# Sheet1.net
KiCad netlist of a schematic drawn in Altium Designer
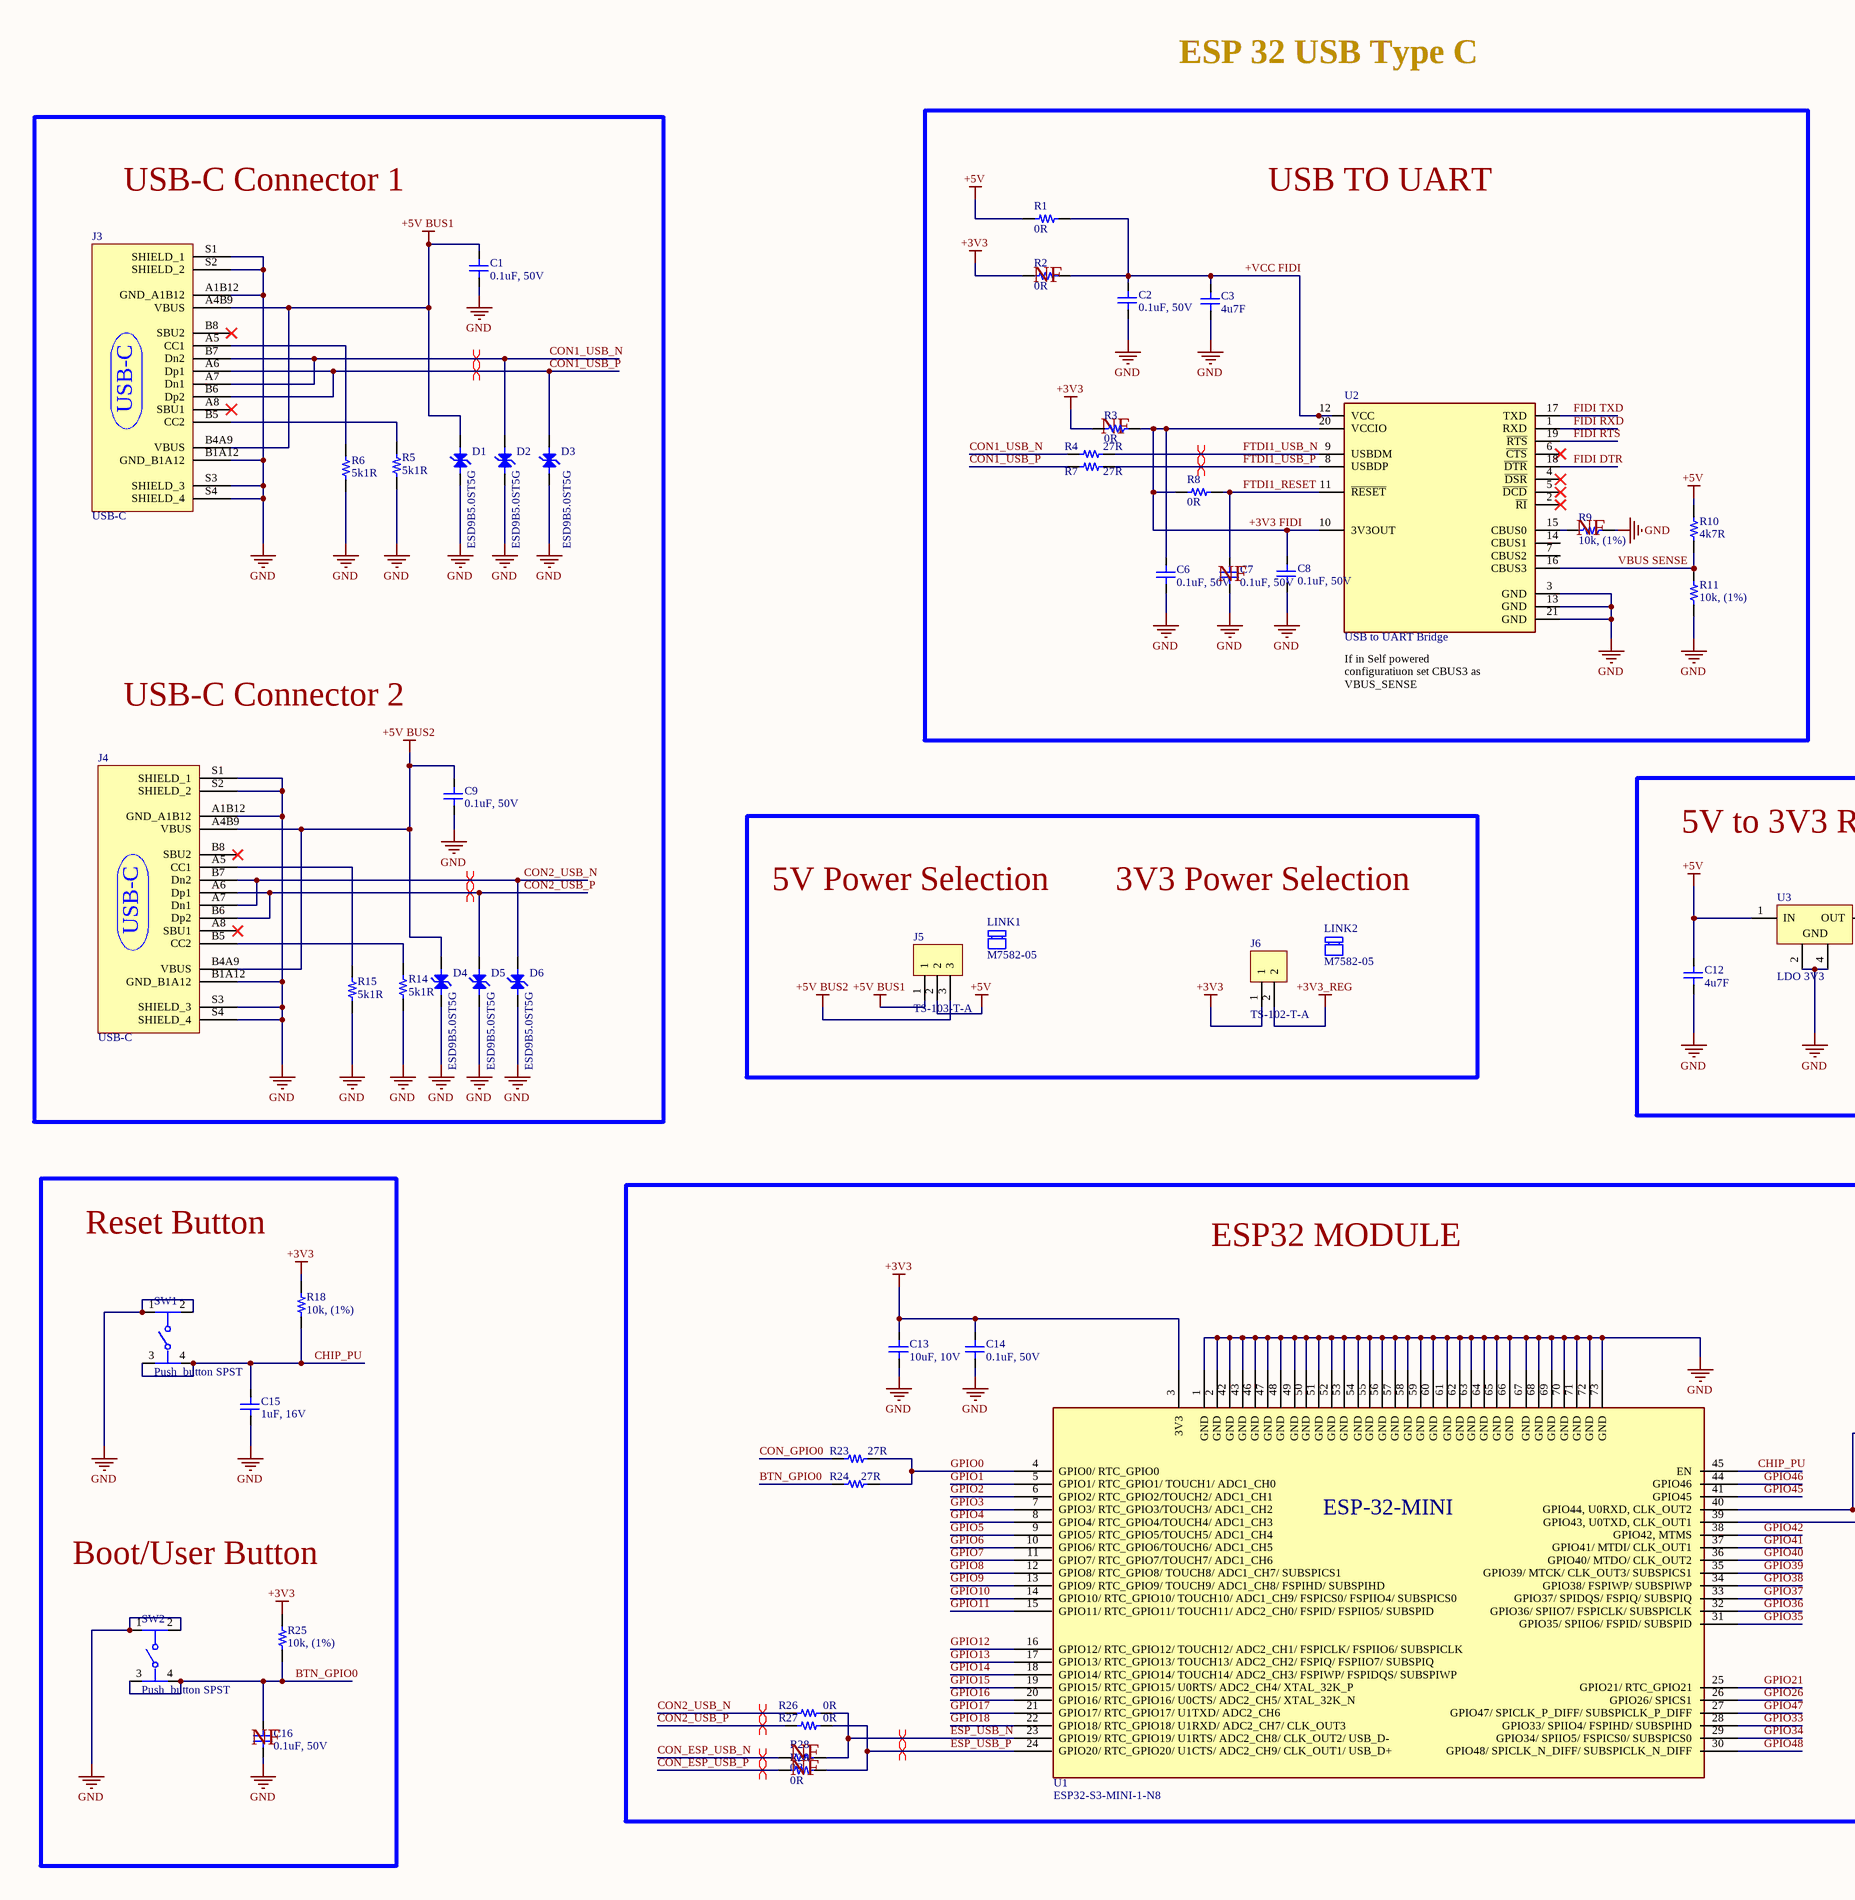
[diagram p0: Sheet1.SchDoc, left]
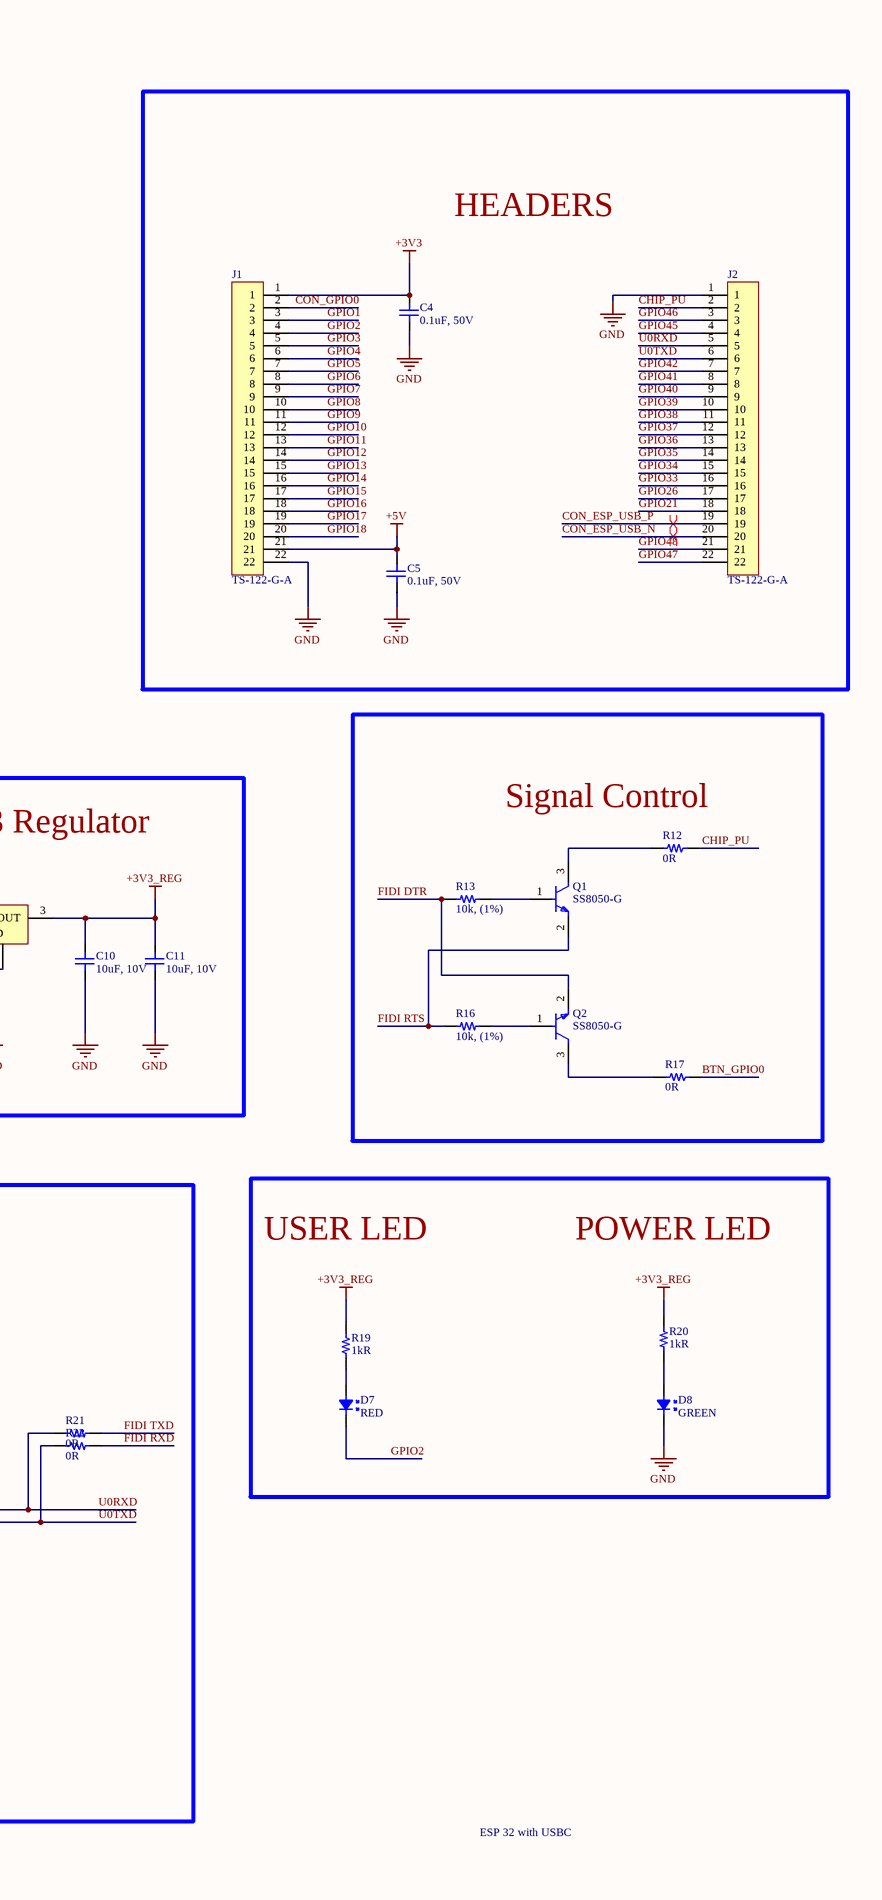
[diagram p1: Sheet1.SchDoc, right]

(export (version "E")
  (design (tool "Eeschema 10.0.6"))
  (components
    (comp (ref "C1")
      (value "0.1uF, 50V")
      (footprint "FP-CL599-IPC_B")
      (description "50V 100nF X7R ±10% 0402 Multilayer Ceramic Capacitors MLCC - SMD/SMT ROHS")
      (fields
        (field (name "MANUFACTURER") "Samsung")
        (field (name "MANUFACTURER PART NUMBER") "CL05B104KB54PNC")
      )
      (libsource (lib "Schlib1") (part "CL05B104KB54PNC"))
    )
    (comp (ref "C2")
      (value "0.1uF, 50V")
      (footprint "FP-CL599-IPC_B")
      (description "50V 100nF X7R ±10% 0402 Multilayer Ceramic Capacitors MLCC - SMD/SMT ROHS")
      (fields
        (field (name "MANUFACTURER") "Samsung")
        (field (name "MANUFACTURER PART NUMBER") "CL05B104KB54PNC")
      )
      (libsource (lib "Schlib1") (part "CL05B104KB54PNC"))
    )
    (comp (ref "C3")
      (value "4u7F")
      (footprint "FP-CL599-IPC_B")
      (description "Multilayer Ceramic Capacitor, 4.7 uF, 10 V, ï¿½ 20%, X5R, 0402 [1005 Metric]")
      (fields
        (field (name "MANUFACTURER") "Samsung")
        (field (name "MANUFACTURER PART NUMBER") "CL05A475MP5NRNC")
      )
      (libsource (lib "Schlib1") (part "CL05A475MP5NRNC"))
    )
    (comp (ref "C4")
      (value "0.1uF, 50V")
      (footprint "FP-CL599-IPC_B")
      (description "50V 100nF X7R ±10% 0402 Multilayer Ceramic Capacitors MLCC - SMD/SMT ROHS")
      (fields
        (field (name "MANUFACTURER") "Samsung")
        (field (name "MANUFACTURER PART NUMBER") "CL05B104KB54PNC")
      )
      (libsource (lib "Schlib1") (part "CL05B104KB54PNC"))
    )
    (comp (ref "C5")
      (value "0.1uF, 50V")
      (footprint "FP-CL599-IPC_B")
      (description "50V 100nF X7R ±10% 0402 Multilayer Ceramic Capacitors MLCC - SMD/SMT ROHS")
      (fields
        (field (name "MANUFACTURER") "Samsung")
        (field (name "MANUFACTURER PART NUMBER") "CL05B104KB54PNC")
      )
      (libsource (lib "Schlib1") (part "CL05B104KB54PNC"))
    )
    (comp (ref "C6")
      (value "0.1uF, 50V")
      (footprint "FP-CL599-IPC_B")
      (description "50V 100nF X7R ±10% 0402 Multilayer Ceramic Capacitors MLCC - SMD/SMT ROHS")
      (fields
        (field (name "MANUFACTURER") "Samsung")
        (field (name "MANUFACTURER PART NUMBER") "CL05B104KB54PNC")
      )
      (libsource (lib "Schlib1") (part "CL05B104KB54PNC"))
    )
    (comp (ref "C7")
      (value "0.1uF, 50V")
      (footprint "FP-CL599-IPC_B")
      (description "50V 100nF X7R ±10% 0402 Multilayer Ceramic Capacitors MLCC - SMD/SMT ROHS")
      (fields
        (field (name "MANUFACTURER") "Samsung")
        (field (name "MANUFACTURER PART NUMBER") "CL05B104KB54PNC")
      )
      (libsource (lib "Schlib1") (part "CL05B104KB54PNC"))
    )
    (comp (ref "C8")
      (value "0.1uF, 50V")
      (footprint "FP-CL599-IPC_B")
      (description "50V 100nF X7R ±10% 0402 Multilayer Ceramic Capacitors MLCC - SMD/SMT ROHS")
      (fields
        (field (name "MANUFACTURER") "Samsung")
        (field (name "MANUFACTURER PART NUMBER") "CL05B104KB54PNC")
      )
      (libsource (lib "Schlib1") (part "CL05B104KB54PNC"))
    )
    (comp (ref "C9")
      (value "0.1uF, 50V")
      (footprint "FP-CL599-IPC_B")
      (description "50V 100nF X7R ±10% 0402 Multilayer Ceramic Capacitors MLCC - SMD/SMT ROHS")
      (fields
        (field (name "MANUFACTURER") "Samsung")
        (field (name "MANUFACTURER PART NUMBER") "CL05B104KB54PNC")
      )
      (libsource (lib "Schlib1") (part "CL05B104KB54PNC"))
    )
    (comp (ref "C10")
      (value "10uF, 10V")
      (footprint "FP-CL599-IPC_B")
      (description "Multilayer Ceramic Capacitor, 10 uF, 10 V, ± 20%, X5R, 0402 [1005 Metric]")
      (fields
        (field (name "MANUFACTURER") "Samsung")
        (field (name "MANUFACTURER PART NUMBER") "CL05A106MP8NUB8")
      )
      (libsource (lib "Schlib1") (part "CL05A106MP8NUB8"))
    )
    (comp (ref "C11")
      (value "10uF, 10V")
      (footprint "FP-CL599-IPC_B")
      (description "Multilayer Ceramic Capacitor, 10 uF, 10 V, ± 20%, X5R, 0402 [1005 Metric]")
      (fields
        (field (name "MANUFACTURER") "Samsung")
        (field (name "MANUFACTURER PART NUMBER") "CL05A106MP8NUB8")
      )
      (libsource (lib "Schlib1") (part "CL05A106MP8NUB8"))
    )
    (comp (ref "C12")
      (value "4u7F")
      (footprint "FP-CL599-IPC_B")
      (description "Multilayer Ceramic Capacitor, 4.7 uF, 10 V, ï¿½ 20%, X5R, 0402 [1005 Metric]")
      (fields
        (field (name "MANUFACTURER") "Samsung")
        (field (name "MANUFACTURER PART NUMBER") "CL05A475MP5NRNC")
      )
      (libsource (lib "Schlib1") (part "CL05A475MP5NRNC"))
    )
    (comp (ref "C13")
      (value "10uF, 10V")
      (footprint "FP-CL599-IPC_B")
      (description "Multilayer Ceramic Capacitor, 10 uF, 10 V, ± 20%, X5R, 0402 [1005 Metric]")
      (fields
        (field (name "MANUFACTURER") "Samsung")
        (field (name "MANUFACTURER PART NUMBER") "CL05A106MP8NUB8")
      )
      (libsource (lib "Schlib1") (part "CL05A106MP8NUB8"))
    )
    (comp (ref "C14")
      (value "0.1uF, 50V")
      (footprint "FP-CL599-IPC_B")
      (description "50V 100nF X7R ±10% 0402 Multilayer Ceramic Capacitors MLCC - SMD/SMT ROHS")
      (fields
        (field (name "MANUFACTURER") "Samsung")
        (field (name "MANUFACTURER PART NUMBER") "CL05B104KB54PNC")
      )
      (libsource (lib "Schlib1") (part "CL05B104KB54PNC"))
    )
    (comp (ref "C15")
      (value "1uF, 16V")
      (footprint "FP-CL599-IPC_B")
      (description "16V 1uF X5R ±10% 0402 Multilayer Ceramic Capacitors MLCC - SMD/SMT ROHS")
      (fields
        (field (name "MANUFACTURER") "Samsung")
        (field (name "MANUFACTURER PART NUMBER") "CL05A105KO5NNNC")
      )
      (libsource (lib "Schlib1") (part "CL05A105KO5NNNC"))
    )
    (comp (ref "C16")
      (value "0.1uF, 50V")
      (footprint "FP-CL599-IPC_B")
      (description "50V 100nF X7R ±10% 0402 Multilayer Ceramic Capacitors MLCC - SMD/SMT ROHS")
      (fields
        (field (name "MANUFACTURER") "Samsung")
        (field (name "MANUFACTURER PART NUMBER") "CL05B104KB54PNC")
      )
      (libsource (lib "Schlib1") (part "CL05B104KB54PNC"))
    )
    (comp (ref "D1")
      (value "ESD9B5.0ST5G")
      (footprint "ONSC-SOD-923-2-514AB-01_V")
      (description "ESD Suppressor TVS Single Bi-Dir ±18kV@Air Gap/±18kV@Contact Disc 2-Pin SOD-923 T/R")
      (fields (field (name "MANUFACTURER") "ON Semiconductor") (field (name "LCSC PART NUMBER") "C316040"))
      (libsource (lib "Schlib1") (part "ESD9B5.0ST5G"))
    )
    (comp (ref "D2")
      (value "ESD9B5.0ST5G")
      (footprint "ONSC-SOD-923-2-514AB-01_V")
      (description "ESD Suppressor TVS Single Bi-Dir ±18kV@Air Gap/±18kV@Contact Disc 2-Pin SOD-923 T/R")
      (fields (field (name "MANUFACTURER") "ON Semiconductor") (field (name "LCSC PART NUMBER") "C316040"))
      (libsource (lib "Schlib1") (part "ESD9B5.0ST5G"))
    )
    (comp (ref "D3")
      (value "ESD9B5.0ST5G")
      (footprint "ONSC-SOD-923-2-514AB-01_V")
      (description "ESD Suppressor TVS Single Bi-Dir ±18kV@Air Gap/±18kV@Contact Disc 2-Pin SOD-923 T/R")
      (fields (field (name "MANUFACTURER") "ON Semiconductor") (field (name "LCSC PART NUMBER") "C316040"))
      (libsource (lib "Schlib1") (part "ESD9B5.0ST5G"))
    )
    (comp (ref "D4")
      (value "ESD9B5.0ST5G")
      (footprint "ONSC-SOD-923-2-514AB-01_V")
      (description "ESD Suppressor TVS Single Bi-Dir ±18kV@Air Gap/±18kV@Contact Disc 2-Pin SOD-923 T/R")
      (fields (field (name "MANUFACTURER") "ON Semiconductor") (field (name "LCSC PART NUMBER") "C316040"))
      (libsource (lib "Schlib1") (part "ESD9B5.0ST5G"))
    )
    (comp (ref "D5")
      (value "ESD9B5.0ST5G")
      (footprint "ONSC-SOD-923-2-514AB-01_V")
      (description "ESD Suppressor TVS Single Bi-Dir ±18kV@Air Gap/±18kV@Contact Disc 2-Pin SOD-923 T/R")
      (fields (field (name "MANUFACTURER") "ON Semiconductor") (field (name "LCSC PART NUMBER") "C316040"))
      (libsource (lib "Schlib1") (part "ESD9B5.0ST5G"))
    )
    (comp (ref "D6")
      (value "ESD9B5.0ST5G")
      (footprint "ONSC-SOD-923-2-514AB-01_V")
      (description "ESD Suppressor TVS Single Bi-Dir ±18kV@Air Gap/±18kV@Contact Disc 2-Pin SOD-923 T/R")
      (fields (field (name "MANUFACTURER") "ON Semiconductor") (field (name "LCSC PART NUMBER") "C316040"))
      (libsource (lib "Schlib1") (part "ESD9B5.0ST5G"))
    )
    (comp (ref "D7")
      (value "RED")
      (footprint "LED-RED-0402")
      (description "LED RED 0402 SMD")
      (fields
        (field (name "MANUFACTURER") "Vishay")
        (field (name "MANUFACTURER PART NUMBER") "VLMS1500-GS08")
      )
      (libsource (lib "Schlib1") (part "VLMS1500-GS08"))
    )
    (comp (ref "D8")
      (value "GREEN")
      (footprint "LED-GREEN-0402")
      (description "LED GREEN 0402 SMD")
      (fields
        (field (name "MANUFACTURER") "Vishay")
        (field (name "MANUFACTURER PART NUMBER") "VLMTG1500-GS08")
      )
      (libsource (lib "Schlib1") (part "VLMTG1500-GS08"))
    )
    (comp (ref "J1")
      (value "TS-122-G-A")
      (footprint "HDR_1x22_2.54MM")
      (description "22 Position Header Connector Post Gold")
      (fields (field (name "MANUFACTURER") "Samtec") (field (name "LCSC PART NUMBER") "C7125323"))
      (libsource (lib "Schlib1") (part "TS-122-G-A"))
    )
    (comp (ref "J2")
      (value "TS-122-G-A")
      (footprint "HDR_1x22_2.54MM")
      (description "22 Position Header Connector Post Gold")
      (fields (field (name "MANUFACTURER") "Samtec") (field (name "LCSC PART NUMBER") "C7125323"))
      (libsource (lib "") (part "TS-122-G-A_1"))
    )
    (comp (ref "J3")
      (value "USB-C")
      (footprint "FP-2171790001-MFG")
      (description "CONN RCP USB2.0 TYP C 24P SMD RA")
      (fields (field (name "MANUFACTURER") "Molex") (field (name "MANUFACTURER PART NUMBER") "217179-0001"))
      (libsource (lib "Schlib1") (part "217179-0001"))
    )
    (comp (ref "J4")
      (value "USB-C")
      (footprint "FP-2171790001-MFG")
      (description "CONN RCP USB2.0 TYP C 24P SMD RA")
      (fields (field (name "MANUFACTURER") "Molex") (field (name "MANUFACTURER PART NUMBER") "217179-0001"))
      (libsource (lib "Schlib1") (part "217179-0001"))
    )
    (comp (ref "J5")
      (value "TS-103-T-A")
      (footprint "HDR_1x3_2.54MM")
      (description "CONN HEADER VERT 3POS 2.54MM")
      (fields (field (name "MANUFACTURER") "Samtec") (field (name "LCSC PART NUMBER") "C6338633"))
      (libsource (lib "Schlib1") (part "TS-103-T-A"))
    )
    (comp (ref "J6")
      (value "TS-102-T-A")
      (footprint "HDR_1x2_2.54MM")
      (description "CONN HEADER VERT 2POS 2.54MM")
      (fields (field (name "MANUFACTURER") "Samtec") (field (name "LCSC PART NUMBER") "C3337950"))
      (libsource (lib "Schlib1") (part "TS-102-T-A"))
    )
    (comp (ref "LINK1")
      (value "M7582-05")
      (description "2.54mm (0.1\") Pitch Open Top Jumper Socket, single use, gold, Black")
      (fields (field (name "MANUFACTURER") "Harwin") (field (name "LCSC PART NUMBER") "C3715643"))
      (libsource (lib "Schlib1") (part "M7582-05"))
    )
    (comp (ref "LINK2")
      (value "M7582-05")
      (description "2.54mm (0.1\") Pitch Open Top Jumper Socket, single use, gold, Black")
      (fields (field (name "MANUFACTURER") "Harwin") (field (name "LCSC PART NUMBER") "C3715643"))
      (libsource (lib "Schlib1") (part "M7582-05"))
    )
    (comp (ref "Q1")
      (value "SS8050-G")
      (footprint "FP-SS8050-G-IPC_B")
      (description "TRANS NPN 25V 1.5A SOT-23-3")
      (fields (field (name "MANUFACTURER") "Comchip") (field (name "LCSC PART NUMBER") "C164886"))
      (libsource (lib "Schlib1") (part "SS8050-G"))
    )
    (comp (ref "Q2")
      (value "SS8050-G")
      (footprint "FP-SS8050-G-IPC_B")
      (description "TRANS NPN 25V 1.5A SOT-23-3")
      (fields (field (name "MANUFACTURER") "Comchip") (field (name "LCSC PART NUMBER") "C164886"))
      (libsource (lib "Schlib1") (part "SS8050-G"))
    )
    (comp (ref "R1")
      (value "0R")
      (footprint "RESC1005X40X25NL05T10")
      (description "62.5mW Thick Film Resistors 50V ±5% 0Ω 0402 Chip Resistor - Surface Mount ROHS")
      (fields
        (field (name "MANUFACTURER") "Yageo")
        (field (name "MANUFACTURER PART NUMBER") "RC0402FR-070RL")
      )
      (libsource (lib "Schlib1") (part "RC0402FR-070RL"))
    )
    (comp (ref "R2")
      (value "0R")
      (footprint "RESC1005X40X25NL05T10")
      (description "62.5mW Thick Film Resistors 50V ±5% 0Ω 0402 Chip Resistor - Surface Mount ROHS")
      (fields
        (field (name "MANUFACTURER") "Yageo")
        (field (name "MANUFACTURER PART NUMBER") "RC0402FR-070RL")
      )
      (libsource (lib "Schlib1") (part "RC0402FR-070RL"))
    )
    (comp (ref "R3")
      (value "0R")
      (footprint "RESC1005X40X25NL05T10")
      (description "62.5mW Thick Film Resistors 50V ±5% 0Ω 0402 Chip Resistor - Surface Mount ROHS")
      (fields
        (field (name "MANUFACTURER") "Yageo")
        (field (name "MANUFACTURER PART NUMBER") "RC0402FR-070RL")
      )
      (libsource (lib "Schlib1") (part "RC0402FR-070RL"))
    )
    (comp (ref "R4")
      (value "27R")
      (footprint "RESC1005X40X25NL05T10")
      (description "62.5mW 27Ω 50V ±1% ±100ppm/℃ Thick Film Resistors 0402 Chip Resistor - Surface Mount ROHS")
      (fields
        (field (name "MANUFACTURER") "Yageo")
        (field (name "MANUFACTURER PART NUMBER") "RC0402FR-0727RL")
      )
      (libsource (lib "Schlib1") (part "RC0402FR-0727RL"))
    )
    (comp (ref "R5")
      (value "5k1R")
      (footprint "RESC1005X40X25NL05T10")
      (description "RES 5.1K OHM 1% 1/16W 0402")
      (fields
        (field (name "MANUFACTURER") "Yageo")
        (field (name "MANUFACTURER PART NUMBER") "RC0402FR-075K1L")
      )
      (libsource (lib "Schlib1") (part "RC0402FR-075K1L"))
    )
    (comp (ref "R6")
      (value "5k1R")
      (footprint "RESC1005X40X25NL05T10")
      (description "RES 5.1K OHM 1% 1/16W 0402")
      (fields
        (field (name "MANUFACTURER") "Yageo")
        (field (name "MANUFACTURER PART NUMBER") "RC0402FR-075K1L")
      )
      (libsource (lib "Schlib1") (part "RC0402FR-075K1L"))
    )
    (comp (ref "R7")
      (value "27R")
      (footprint "RESC1005X40X25NL05T10")
      (description "62.5mW 27Ω 50V ±1% ±100ppm/℃ Thick Film Resistors 0402 Chip Resistor - Surface Mount ROHS")
      (fields
        (field (name "MANUFACTURER") "Yageo")
        (field (name "MANUFACTURER PART NUMBER") "RC0402FR-0727RL")
      )
      (libsource (lib "Schlib1") (part "RC0402FR-0727RL"))
    )
    (comp (ref "R8")
      (value "0R")
      (footprint "RESC1005X40X25NL05T10")
      (description "62.5mW Thick Film Resistors 50V ±5% 0Ω 0402 Chip Resistor - Surface Mount ROHS")
      (fields
        (field (name "MANUFACTURER") "Yageo")
        (field (name "MANUFACTURER PART NUMBER") "RC0402FR-070RL")
      )
      (libsource (lib "Schlib1") (part "RC0402FR-070RL"))
    )
    (comp (ref "R9")
      (value "10k, (1%)")
      (footprint "RESC1005X40X25NL05T10")
      (description "SMD Chip Resistor, 10 kOhm, ï¿½ 1%, 62.5 mW, 0402 [1005 Metric], Thick Film, General Purpose")
      (fields
        (field (name "MANUFACTURER") "Yageo")
        (field (name "MANUFACTURER PART NUMBER") "AC0402FR-0710KL")
      )
      (libsource (lib "Schlib1") (part "AC0402FR-0710KL"))
    )
    (comp (ref "R10")
      (value "4k7R")
      (footprint "RESC1005X40X25NL05T10")
      (description "RES 4.7K OHM 5% 1/16W 0402")
      (fields
        (field (name "MANUFACTURER") "Yageo")
        (field (name "MANUFACTURER PART NUMBER") "RC0402JR-074K7L")
      )
      (libsource (lib "Schlib1") (part "RC0402JR-074K7L"))
    )
    (comp (ref "R11")
      (value "10k, (1%)")
      (footprint "RESC1005X40X25NL05T10")
      (description "SMD Chip Resistor, 10 kOhm, ï¿½ 1%, 62.5 mW, 0402 [1005 Metric], Thick Film, General Purpose")
      (fields
        (field (name "MANUFACTURER") "Yageo")
        (field (name "MANUFACTURER PART NUMBER") "AC0402FR-0710KL")
      )
      (libsource (lib "Schlib1") (part "AC0402FR-0710KL"))
    )
    (comp (ref "R12")
      (value "0R")
      (footprint "RESC1005X40X25NL05T10")
      (description "62.5mW Thick Film Resistors 50V ±5% 0Ω 0402 Chip Resistor - Surface Mount ROHS")
      (fields
        (field (name "MANUFACTURER") "Yageo")
        (field (name "MANUFACTURER PART NUMBER") "RC0402FR-070RL")
      )
      (libsource (lib "Schlib1") (part "RC0402FR-070RL"))
    )
    (comp (ref "R13")
      (value "10k, (1%)")
      (footprint "RESC1005X40X25NL05T10")
      (description "SMD Chip Resistor, 10 kOhm, ï¿½ 1%, 62.5 mW, 0402 [1005 Metric], Thick Film, General Purpose")
      (fields
        (field (name "MANUFACTURER") "Yageo")
        (field (name "MANUFACTURER PART NUMBER") "AC0402FR-0710KL")
      )
      (libsource (lib "Schlib1") (part "AC0402FR-0710KL"))
    )
    (comp (ref "R14")
      (value "5k1R")
      (footprint "RESC1005X40X25NL05T10")
      (description "RES 5.1K OHM 1% 1/16W 0402")
      (fields
        (field (name "MANUFACTURER") "Yageo")
        (field (name "MANUFACTURER PART NUMBER") "RC0402FR-075K1L")
      )
      (libsource (lib "Schlib1") (part "RC0402FR-075K1L"))
    )
    (comp (ref "R15")
      (value "5k1R")
      (footprint "RESC1005X40X25NL05T10")
      (description "RES 5.1K OHM 1% 1/16W 0402")
      (fields
        (field (name "MANUFACTURER") "Yageo")
        (field (name "MANUFACTURER PART NUMBER") "RC0402FR-075K1L")
      )
      (libsource (lib "Schlib1") (part "RC0402FR-075K1L"))
    )
    (comp (ref "R16")
      (value "10k, (1%)")
      (footprint "RESC1005X40X25NL05T10")
      (description "SMD Chip Resistor, 10 kOhm, ï¿½ 1%, 62.5 mW, 0402 [1005 Metric], Thick Film, General Purpose")
      (fields
        (field (name "MANUFACTURER") "Yageo")
        (field (name "MANUFACTURER PART NUMBER") "AC0402FR-0710KL")
      )
      (libsource (lib "Schlib1") (part "AC0402FR-0710KL"))
    )
    (comp (ref "R17")
      (value "0R")
      (footprint "RESC1005X40X25NL05T10")
      (description "62.5mW Thick Film Resistors 50V ±5% 0Ω 0402 Chip Resistor - Surface Mount ROHS")
      (fields
        (field (name "MANUFACTURER") "Yageo")
        (field (name "MANUFACTURER PART NUMBER") "RC0402FR-070RL")
      )
      (libsource (lib "Schlib1") (part "RC0402FR-070RL"))
    )
    (comp (ref "R18")
      (value "10k, (1%)")
      (footprint "RESC1005X40X25NL05T10")
      (description "SMD Chip Resistor, 10 kOhm, ï¿½ 1%, 62.5 mW, 0402 [1005 Metric], Thick Film, General Purpose")
      (fields
        (field (name "MANUFACTURER") "Yageo")
        (field (name "MANUFACTURER PART NUMBER") "AC0402FR-0710KL")
      )
      (libsource (lib "Schlib1") (part "AC0402FR-0710KL"))
    )
    (comp (ref "R19")
      (value "1kR")
      (footprint "RESC1005X40X25NL05T10")
      (description "RES 1K OHM 5% 1/16W 0402")
      (fields
        (field (name "MANUFACTURER") "Yageo")
        (field (name "MANUFACTURER PART NUMBER") "RC0402JR-071KL")
      )
      (libsource (lib "Schlib1") (part "RC0402JR-071KL"))
    )
    (comp (ref "R20")
      (value "1kR")
      (footprint "RESC1005X40X25NL05T10")
      (description "RES 1K OHM 5% 1/16W 0402")
      (fields
        (field (name "MANUFACTURER") "Yageo")
        (field (name "MANUFACTURER PART NUMBER") "RC0402JR-071KL")
      )
      (libsource (lib "Schlib1") (part "RC0402JR-071KL"))
    )
    (comp (ref "R21")
      (value "0R")
      (footprint "RESC1005X40X25NL05T10")
      (description "62.5mW Thick Film Resistors 50V ±5% 0Ω 0402 Chip Resistor - Surface Mount ROHS")
      (fields
        (field (name "MANUFACTURER") "Yageo")
        (field (name "MANUFACTURER PART NUMBER") "RC0402FR-070RL")
      )
      (libsource (lib "Schlib1") (part "RC0402FR-070RL"))
    )
    (comp (ref "R22")
      (value "0R")
      (footprint "RESC1005X40X25NL05T10")
      (description "62.5mW Thick Film Resistors 50V ±5% 0Ω 0402 Chip Resistor - Surface Mount ROHS")
      (fields
        (field (name "MANUFACTURER") "Yageo")
        (field (name "MANUFACTURER PART NUMBER") "RC0402FR-070RL")
      )
      (libsource (lib "Schlib1") (part "RC0402FR-070RL"))
    )
    (comp (ref "R23")
      (value "27R")
      (footprint "RESC1005X40X25NL05T10")
      (description "62.5mW 27Ω 50V ±1% ±100ppm/℃ Thick Film Resistors 0402 Chip Resistor - Surface Mount ROHS")
      (fields
        (field (name "MANUFACTURER") "Yageo")
        (field (name "MANUFACTURER PART NUMBER") "RC0402FR-0727RL")
      )
      (libsource (lib "Schlib1") (part "RC0402FR-0727RL"))
    )
    (comp (ref "R24")
      (value "27R")
      (footprint "RESC1005X40X25NL05T10")
      (description "62.5mW 27Ω 50V ±1% ±100ppm/℃ Thick Film Resistors 0402 Chip Resistor - Surface Mount ROHS")
      (fields
        (field (name "MANUFACTURER") "Yageo")
        (field (name "MANUFACTURER PART NUMBER") "RC0402FR-0727RL")
      )
      (libsource (lib "Schlib1") (part "RC0402FR-0727RL"))
    )
    (comp (ref "R25")
      (value "10k, (1%)")
      (footprint "RESC1005X40X25NL05T10")
      (description "SMD Chip Resistor, 10 kOhm, ï¿½ 1%, 62.5 mW, 0402 [1005 Metric], Thick Film, General Purpose")
      (fields
        (field (name "MANUFACTURER") "Yageo")
        (field (name "MANUFACTURER PART NUMBER") "AC0402FR-0710KL")
      )
      (libsource (lib "Schlib1") (part "AC0402FR-0710KL"))
    )
    (comp (ref "R26")
      (value "0R")
      (footprint "RESC1005X40X25NL05T10")
      (description "62.5mW Thick Film Resistors 50V ±5% 0Ω 0402 Chip Resistor - Surface Mount ROHS")
      (fields
        (field (name "MANUFACTURER") "Yageo")
        (field (name "MANUFACTURER PART NUMBER") "RC0402FR-070RL")
      )
      (libsource (lib "Schlib1") (part "RC0402FR-070RL"))
    )
    (comp (ref "R27")
      (value "0R")
      (footprint "RESC1005X40X25NL05T10")
      (description "62.5mW Thick Film Resistors 50V ±5% 0Ω 0402 Chip Resistor - Surface Mount ROHS")
      (fields
        (field (name "MANUFACTURER") "Yageo")
        (field (name "MANUFACTURER PART NUMBER") "RC0402FR-070RL")
      )
      (libsource (lib "Schlib1") (part "RC0402FR-070RL"))
    )
    (comp (ref "R28")
      (value "0R")
      (footprint "RESC1005X40X25NL05T10")
      (description "62.5mW Thick Film Resistors 50V ±5% 0Ω 0402 Chip Resistor - Surface Mount ROHS")
      (fields
        (field (name "MANUFACTURER") "Yageo")
        (field (name "MANUFACTURER PART NUMBER") "RC0402FR-070RL")
      )
      (libsource (lib "Schlib1") (part "RC0402FR-070RL"))
    )
    (comp (ref "R29")
      (value "0R")
      (footprint "RESC1005X40X25NL05T10")
      (description "62.5mW Thick Film Resistors 50V ±5% 0Ω 0402 Chip Resistor - Surface Mount ROHS")
      (fields
        (field (name "MANUFACTURER") "Yageo")
        (field (name "MANUFACTURER PART NUMBER") "RC0402FR-070RL")
      )
      (libsource (lib "Schlib1") (part "RC0402FR-070RL"))
    )
    (comp (ref "SW1")
      (value "Push  button SPST")
      (footprint "FP-PTS645SH50SMTR92LFS-MFG")
      (description "6mm 5mm Round Button 50mA Standing paste 6mm SPST 200gf 12V SMD,6x6mm Tactile Switches ROHS")
      (fields
        (field (name "MANUFACTURER") "ITT C&K")
        (field (name "MANUFACTURER PART NUMBER") "PTS645SH50SMTR92LFS")
      )
      (libsource (lib "Schlib1") (part "PTS645SH50SMTR92LFS"))
    )
    (comp (ref "SW2")
      (value "Push  button SPST")
      (footprint "FP-PTS645SH50SMTR92LFS-MFG")
      (description "6mm 5mm Round Button 50mA Standing paste 6mm SPST 200gf 12V SMD,6x6mm Tactile Switches ROHS")
      (fields
        (field (name "MANUFACTURER") "ITT C&K")
        (field (name "MANUFACTURER PART NUMBER") "PTS645SH50SMTR92LFS")
      )
      (libsource (lib "Schlib1") (part "PTS645SH50SMTR92LFS"))
    )
    (comp (ref "U1")
      (value "ESP32-S3-MINI-1-N8")
      (footprint "XCVR_ESP32-S3-MINI-1-N8")
      (description "SMD module, ESP32-S3FN8, 8 MB SPI flash, PCB antenna")
      (fields (field (name "MANUFACTURER") "Espressif Systems") (field (name "LCSC PART NUMBER") "C2913206"))
      (libsource (lib "Schlib1") (part "ESP32-S3-MINI-1-N8"))
    )
    (comp (ref "U2")
      (value "USB to UART Bridge")
      (footprint "FP-QFN-20-IPC_B")
      (description "USB to Full Handshake UART Interface QFN20 Reel (not offered in your region)")
      (fields (field (name "MANUFACTURER") "FTDI") (field (name "MANUFACTURER PART NUMBER") "FT231XQ-R"))
      (libsource (lib "Schlib1") (part "FT231XQ-R"))
    )
    (comp (ref "U3")
      (value "LDO 3V3")
      (footprint "DCY0004A_N")
      (description "IC REG LINEAR 3.3V 1.5A SOT223-4")
      (fields
        (field (name "MANUFACTURER") "Texas Instruments")
        (field (name "MANUFACTURER PART NUMBER") "TL1963A-33DCYR")
      )
      (libsource (lib "Schlib1") (part "TL1963A-33DCYR"))
    )
  )
  (nets
    (net (code "1") (name "+3V3") (class "Default")
      (node (ref "C13") (pin "2") (pinfunction "2_2") (pintype "passive"))
      (node (ref "C14") (pin "2") (pinfunction "2_2") (pintype "passive"))
      (node (ref "C4") (pin "2") (pinfunction "2_2") (pintype "passive"))
      (node (ref "J1") (pin "1") (pinfunction "1_1") (pintype "passive"))
      (node (ref "J6") (pin "1") (pinfunction "1_1") (pintype "passive"))
      (node (ref "R18") (pin "2") (pinfunction "2_2") (pintype "passive"))
      (node (ref "R2") (pin "1") (pinfunction "1_1") (pintype "passive"))
      (node (ref "R25") (pin "2") (pinfunction "2_2") (pintype "passive"))
      (node (ref "R3") (pin "1") (pinfunction "1_1") (pintype "passive"))
      (node (ref "U1") (pin "3") (pinfunction "3V3_3") (pintype "passive"))
    )
    (net (code "2") (name "+3V3_REG") (class "Default")
      (node (ref "C10") (pin "2") (pinfunction "2_2") (pintype "passive"))
      (node (ref "C11") (pin "2") (pinfunction "2_2") (pintype "passive"))
      (node (ref "J6") (pin "2") (pinfunction "2_2") (pintype "passive"))
      (node (ref "R19") (pin "2") (pinfunction "2_2") (pintype "passive"))
      (node (ref "R20") (pin "2") (pinfunction "2_2") (pintype "passive"))
      (node (ref "U3") (pin "3") (pinfunction "OUT_3") (pintype "power_in"))
    )
    (net (code "3") (name "+5V") (class "Default")
      (node (ref "C12") (pin "2") (pinfunction "2_2") (pintype "passive"))
      (node (ref "C5") (pin "2") (pinfunction "2_2") (pintype "passive"))
      (node (ref "J1") (pin "21") (pinfunction "21_21") (pintype "passive"))
      (node (ref "J5") (pin "2") (pinfunction "2_2") (pintype "passive"))
      (node (ref "R1") (pin "1") (pinfunction "1_1") (pintype "passive"))
      (node (ref "R10") (pin "2") (pinfunction "2_2") (pintype "passive"))
      (node (ref "U3") (pin "1") (pinfunction "IN_1") (pintype "power_in"))
    )
    (net (code "4") (name "+5V BUS1") (class "Default")
      (node (ref "C1") (pin "2") (pinfunction "2_2") (pintype "passive"))
      (node (ref "D1") (pin "2") (pinfunction "2_2") (pintype "passive"))
      (node (ref "J3") (pin "A4B9") (pinfunction "VBUS_A4B9") (pintype "passive"))
      (node (ref "J3") (pin "B4A9") (pinfunction "VBUS_B4A9") (pintype "passive"))
      (node (ref "J5") (pin "1") (pinfunction "1_1") (pintype "passive"))
    )
    (net (code "5") (name "+5V BUS2") (class "Default")
      (node (ref "C9") (pin "2") (pinfunction "2_2") (pintype "passive"))
      (node (ref "D4") (pin "2") (pinfunction "2_2") (pintype "passive"))
      (node (ref "J4") (pin "A4B9") (pinfunction "VBUS_A4B9") (pintype "passive"))
      (node (ref "J4") (pin "B4A9") (pinfunction "VBUS_B4A9") (pintype "passive"))
      (node (ref "J5") (pin "3") (pinfunction "3_3") (pintype "passive"))
    )
    (net (code "6") (name "/+3V3 FIDI") (class "Default")
      (node (ref "C6") (pin "2") (pinfunction "2_2") (pintype "passive"))
      (node (ref "C8") (pin "2") (pinfunction "2_2") (pintype "passive"))
      (node (ref "R3") (pin "2") (pinfunction "2_2") (pintype "passive"))
      (node (ref "R8") (pin "1") (pinfunction "1_1") (pintype "passive"))
      (node (ref "U2") (pin "10") (pinfunction "3V3OUT_10") (pintype "passive"))
      (node (ref "U2") (pin "20") (pinfunction "VCCIO_20") (pintype "passive"))
    )
    (net (code "7") (name "/+VCC FIDI") (class "Default")
      (node (ref "C2") (pin "2") (pinfunction "2_2") (pintype "passive"))
      (node (ref "C3") (pin "2") (pinfunction "2_2") (pintype "passive"))
      (node (ref "R1") (pin "2") (pinfunction "2_2") (pintype "passive"))
      (node (ref "R2") (pin "2") (pinfunction "2_2") (pintype "passive"))
      (node (ref "U2") (pin "12") (pinfunction "VCC_12") (pintype "passive"))
    )
    (net (code "8") (name "/BTN_GPIO0") (class "Default")
      (node (ref "C16") (pin "2") (pinfunction "2_2") (pintype "passive"))
      (node (ref "R17") (pin "2") (pinfunction "2_2") (pintype "passive"))
      (node (ref "R24") (pin "1") (pinfunction "1_1") (pintype "passive"))
      (node (ref "R25") (pin "1") (pinfunction "1_1") (pintype "passive"))
      (node (ref "SW2") (pin "3") (pinfunction "3_3") (pintype "passive"))
      (node (ref "SW2") (pin "4") (pinfunction "4_4") (pintype "passive"))
    )
    (net (code "9") (name "/CHIP_PU") (class "Default")
      (node (ref "C15") (pin "2") (pinfunction "2_2") (pintype "passive"))
      (node (ref "J2") (pin "2") (pinfunction "2_2") (pintype "passive"))
      (node (ref "R12") (pin "2") (pinfunction "2_2") (pintype "passive"))
      (node (ref "R18") (pin "1") (pinfunction "1_1") (pintype "passive"))
      (node (ref "SW1") (pin "3") (pinfunction "3_3") (pintype "passive"))
      (node (ref "SW1") (pin "4") (pinfunction "4_4") (pintype "passive"))
      (node (ref "U1") (pin "45") (pinfunction "EN_45") (pintype "passive"))
    )
    (net (code "10") (name "/CON1_USB_N") (class "Default")
      (node (ref "D2") (pin "2") (pinfunction "2_2") (pintype "passive"))
      (node (ref "J3") (pin "A7") (pinfunction "Dn1_A7") (pintype "passive"))
      (node (ref "J3") (pin "B7") (pinfunction "Dn2_B7") (pintype "passive"))
      (node (ref "R4") (pin "1") (pinfunction "1_1") (pintype "passive"))
    )
    (net (code "11") (name "/CON1_USB_P") (class "Default")
      (node (ref "D3") (pin "2") (pinfunction "2_2") (pintype "passive"))
      (node (ref "J3") (pin "A6") (pinfunction "Dp1_A6") (pintype "passive"))
      (node (ref "J3") (pin "B6") (pinfunction "Dp2_B6") (pintype "passive"))
      (node (ref "R7") (pin "1") (pinfunction "1_1") (pintype "passive"))
    )
    (net (code "12") (name "/CON2_USB_N") (class "Default")
      (node (ref "D6") (pin "2") (pinfunction "2_2") (pintype "passive"))
      (node (ref "J4") (pin "A7") (pinfunction "Dn1_A7") (pintype "passive"))
      (node (ref "J4") (pin "B7") (pinfunction "Dn2_B7") (pintype "passive"))
      (node (ref "R26") (pin "1") (pinfunction "1_1") (pintype "passive"))
    )
    (net (code "13") (name "/CON2_USB_P") (class "Default")
      (node (ref "D5") (pin "2") (pinfunction "2_2") (pintype "passive"))
      (node (ref "J4") (pin "A6") (pinfunction "Dp1_A6") (pintype "passive"))
      (node (ref "J4") (pin "B6") (pinfunction "Dp2_B6") (pintype "passive"))
      (node (ref "R27") (pin "1") (pinfunction "1_1") (pintype "passive"))
    )
    (net (code "14") (name "/CON_ESP_USB_N") (class "Default")
      (node (ref "J2") (pin "20") (pinfunction "20_20") (pintype "passive"))
      (node (ref "R28") (pin "1") (pinfunction "1_1") (pintype "passive"))
    )
    (net (code "15") (name "/CON_ESP_USB_P") (class "Default")
      (node (ref "J2") (pin "19") (pinfunction "19_19") (pintype "passive"))
      (node (ref "R29") (pin "1") (pinfunction "1_1") (pintype "passive"))
    )
    (net (code "16") (name "/CON_GPIO0") (class "Default")
      (node (ref "J1") (pin "2") (pinfunction "2_2") (pintype "passive"))
      (node (ref "R23") (pin "1") (pinfunction "1_1") (pintype "passive"))
    )
    (net (code "17") (name "/ESP_USB_N") (class "Default")
      (node (ref "R26") (pin "2") (pinfunction "2_2") (pintype "passive"))
      (node (ref "R28") (pin "2") (pinfunction "2_2") (pintype "passive"))
      (node (ref "U1") (pin "23") (pinfunction "GPIO19/_RTC_GPIO19/_U1RTS/_ADC2_CH8/_CLK_OUT2/_USB_D-_23") (pintype "passive"))
    )
    (net (code "18") (name "/ESP_USB_P") (class "Default")
      (node (ref "R27") (pin "2") (pinfunction "2_2") (pintype "passive"))
      (node (ref "R29") (pin "2") (pinfunction "2_2") (pintype "passive"))
      (node (ref "U1") (pin "24") (pinfunction "GPIO20/_RTC_GPIO20/_U1CTS/_ADC2_CH9/_CLK_OUT1/_USB_D+_24") (pintype "passive"))
    )
    (net (code "19") (name "/FIDI DTR") (class "Default")
      (node (ref "Q2") (pin "2") (pinfunction "E_2") (pintype "passive"))
      (node (ref "R13") (pin "1") (pinfunction "1_1") (pintype "passive"))
      (node (ref "U2") (pin "18") (pinfunction "~{DTR}_18") (pintype "passive"))
    )
    (net (code "20") (name "/FIDI RTS") (class "Default")
      (node (ref "Q1") (pin "2") (pinfunction "E_2") (pintype "passive"))
      (node (ref "R16") (pin "1") (pinfunction "1_1") (pintype "passive"))
      (node (ref "U2") (pin "19") (pinfunction "~{RTS}_19") (pintype "passive"))
    )
    (net (code "21") (name "/FIDI RXD") (class "Default")
      (node (ref "R22") (pin "2") (pinfunction "2_2") (pintype "passive"))
      (node (ref "U2") (pin "1") (pinfunction "RXD_1") (pintype "passive"))
    )
    (net (code "22") (name "/FIDI TXD") (class "Default")
      (node (ref "R21") (pin "2") (pinfunction "2_2") (pintype "passive"))
      (node (ref "U2") (pin "17") (pinfunction "TXD_17") (pintype "passive"))
    )
    (net (code "23") (name "/FTDI1_RESET") (class "Default")
      (node (ref "C7") (pin "2") (pinfunction "2_2") (pintype "passive"))
      (node (ref "R8") (pin "2") (pinfunction "2_2") (pintype "passive"))
      (node (ref "U2") (pin "11") (pinfunction "~{RESET}_11") (pintype "passive"))
    )
    (net (code "24") (name "/FTDI1_USB_N") (class "Default")
      (node (ref "R4") (pin "2") (pinfunction "2_2") (pintype "passive"))
      (node (ref "U2") (pin "9") (pinfunction "USBDM_9") (pintype "passive"))
    )
    (net (code "25") (name "/FTDI1_USB_P") (class "Default")
      (node (ref "R7") (pin "2") (pinfunction "2_2") (pintype "passive"))
      (node (ref "U2") (pin "8") (pinfunction "USBDP_8") (pintype "passive"))
    )
    (net (code "26") (name "/GPIO0") (class "Default")
      (node (ref "R23") (pin "2") (pinfunction "2_2") (pintype "passive"))
      (node (ref "R24") (pin "2") (pinfunction "2_2") (pintype "passive"))
      (node (ref "U1") (pin "4") (pinfunction "GPIO0/_RTC_GPIO0_4") (pintype "passive"))
    )
    (net (code "27") (name "/GPIO1") (class "Default")
      (node (ref "J1") (pin "3") (pinfunction "3_3") (pintype "passive"))
      (node (ref "U1") (pin "5") (pinfunction "GPIO1/_RTC_GPIO1/_TOUCH1/_ADC1_CH0_5") (pintype "passive"))
    )
    (net (code "28") (name "/GPIO2") (class "Default")
      (node (ref "D7") (pin "2") (pinfunction "2_2") (pintype "passive"))
      (node (ref "J1") (pin "4") (pinfunction "4_4") (pintype "passive"))
      (node (ref "U1") (pin "6") (pinfunction "GPIO2/_RTC_GPIO2/TOUCH2/_ADC1_CH1_6") (pintype "passive"))
    )
    (net (code "29") (name "/GPIO3") (class "Default")
      (node (ref "J1") (pin "5") (pinfunction "5_5") (pintype "passive"))
      (node (ref "U1") (pin "7") (pinfunction "GPIO3/_RTC_GPIO3/TOUCH3/_ADC1_CH2_7") (pintype "passive"))
    )
    (net (code "30") (name "/GPIO4") (class "Default")
      (node (ref "J1") (pin "6") (pinfunction "6_6") (pintype "passive"))
      (node (ref "U1") (pin "8") (pinfunction "GPIO4/_RTC_GPIO4/TOUCH4/_ADC1_CH3_8") (pintype "passive"))
    )
    (net (code "31") (name "/GPIO5") (class "Default")
      (node (ref "J1") (pin "7") (pinfunction "7_7") (pintype "passive"))
      (node (ref "U1") (pin "9") (pinfunction "GPIO5/_RTC_GPIO5/TOUCH5/_ADC1_CH4_9") (pintype "passive"))
    )
    (net (code "32") (name "/GPIO6") (class "Default")
      (node (ref "J1") (pin "8") (pinfunction "8_8") (pintype "passive"))
      (node (ref "U1") (pin "10") (pinfunction "GPIO6/_RTC_GPIO6/TOUCH6/_ADC1_CH5_10") (pintype "passive"))
    )
    (net (code "33") (name "/GPIO7") (class "Default")
      (node (ref "J1") (pin "9") (pinfunction "9_9") (pintype "passive"))
      (node (ref "U1") (pin "11") (pinfunction "GPIO7/_RTC_GPIO7/TOUCH7/_ADC1_CH6_11") (pintype "passive"))
    )
    (net (code "34") (name "/GPIO8") (class "Default")
      (node (ref "J1") (pin "10") (pinfunction "10_10") (pintype "passive"))
      (node (ref "U1") (pin "12") (pinfunction "GPIO8/_RTC_GPIO8/_TOUCH8/_ADC1_CH7/_SUBSPICS1_12") (pintype "passive"))
    )
    (net (code "35") (name "/GPIO9") (class "Default")
      (node (ref "J1") (pin "11") (pinfunction "11_11") (pintype "passive"))
      (node (ref "U1") (pin "13") (pinfunction "GPIO9/_RTC_GPIO9/_TOUCH9/_ADC1_CH8/_FSPIHD/_SUBSPIHD_13") (pintype "passive"))
    )
    (net (code "36") (name "/GPIO10") (class "Default")
      (node (ref "J1") (pin "12") (pinfunction "12_12") (pintype "passive"))
      (node (ref "U1") (pin "14") (pinfunction "GPIO10/_RTC_GPIO10/_TOUCH10/_ADC1_CH9/_FSPICS0/_FSPIIO4/_SUBSPICS0_14") (pintype "passive"))
    )
    (net (code "37") (name "/GPIO11") (class "Default")
      (node (ref "J1") (pin "13") (pinfunction "13_13") (pintype "passive"))
      (node (ref "U1") (pin "15") (pinfunction "GPIO11/_RTC_GPIO11/_TOUCH11/_ADC2_CH0/_FSPID/_FSPIIO5/_SUBSPID_15") (pintype "passive"))
    )
    (net (code "38") (name "/GPIO12") (class "Default")
      (node (ref "J1") (pin "14") (pinfunction "14_14") (pintype "passive"))
      (node (ref "U1") (pin "16") (pinfunction "GPIO12/_RTC_GPIO12/_TOUCH12/_ADC2_CH1/_FSPICLK/_FSPIIO6/_SUBSPICLK_16") (pintype "passive"))
    )
    (net (code "39") (name "/GPIO13") (class "Default")
      (node (ref "J1") (pin "15") (pinfunction "15_15") (pintype "passive"))
      (node (ref "U1") (pin "17") (pinfunction "GPIO13/_RTC_GPIO13/_TOUCH13/_ADC2_CH2/_FSPIQ/_FSPIIO7/_SUBSPIQ_17") (pintype "passive"))
    )
    (net (code "40") (name "/GPIO14") (class "Default")
      (node (ref "J1") (pin "16") (pinfunction "16_16") (pintype "passive"))
      (node (ref "U1") (pin "18") (pinfunction "GPIO14/_RTC_GPIO14/_TOUCH14/_ADC2_CH3/_FSPIWP/_FSPIDQS/_SUBSPIWP_18") (pintype "passive"))
    )
    (net (code "41") (name "/GPIO15") (class "Default")
      (node (ref "J1") (pin "17") (pinfunction "17_17") (pintype "passive"))
      (node (ref "U1") (pin "19") (pinfunction "GPIO15/_RTC_GPIO15/_U0RTS/_ADC2_CH4/_XTAL_32K_P_19") (pintype "passive"))
    )
    (net (code "42") (name "/GPIO16") (class "Default")
      (node (ref "J1") (pin "18") (pinfunction "18_18") (pintype "passive"))
      (node (ref "U1") (pin "20") (pinfunction "GPIO16/_RTC_GPIO16/_U0CTS/_ADC2_CH5/_XTAL_32K_N_20") (pintype "passive"))
    )
    (net (code "43") (name "/GPIO17") (class "Default")
      (node (ref "J1") (pin "19") (pinfunction "19_19") (pintype "passive"))
      (node (ref "U1") (pin "21") (pinfunction "GPIO17/_RTC_GPIO17/_U1TXD/_ADC2_CH6_21") (pintype "passive"))
    )
    (net (code "44") (name "/GPIO18") (class "Default")
      (node (ref "J1") (pin "20") (pinfunction "20_20") (pintype "passive"))
      (node (ref "U1") (pin "22") (pinfunction "GPIO18/_RTC_GPIO18/_U1RXD/_ADC2_CH7/_CLK_OUT3_22") (pintype "passive"))
    )
    (net (code "45") (name "/GPIO21") (class "Default")
      (node (ref "J2") (pin "18") (pinfunction "18_18") (pintype "passive"))
      (node (ref "U1") (pin "25") (pinfunction "GPIO21/_RTC_GPIO21_25") (pintype "passive"))
    )
    (net (code "46") (name "/GPIO26") (class "Default")
      (node (ref "J2") (pin "17") (pinfunction "17_17") (pintype "passive"))
      (node (ref "U1") (pin "26") (pinfunction "GPIO26/_SPICS1_26") (pintype "passive"))
    )
    (net (code "47") (name "/GPIO33") (class "Default")
      (node (ref "J2") (pin "16") (pinfunction "16_16") (pintype "passive"))
      (node (ref "U1") (pin "28") (pinfunction "GPIO33/_SPIIO4/_FSPIHD/_SUBSPIHD_28") (pintype "passive"))
    )
    (net (code "48") (name "/GPIO34") (class "Default")
      (node (ref "J2") (pin "15") (pinfunction "15_15") (pintype "passive"))
      (node (ref "U1") (pin "29") (pinfunction "GPIO34/_SPIIO5/_FSPICS0/_SUBSPICS0_29") (pintype "passive"))
    )
    (net (code "49") (name "/GPIO35") (class "Default")
      (node (ref "J2") (pin "14") (pinfunction "14_14") (pintype "passive"))
      (node (ref "U1") (pin "31") (pinfunction "GPIO35/_SPIIO6/_FSPID/_SUBSPID_31") (pintype "passive"))
    )
    (net (code "50") (name "/GPIO36") (class "Default")
      (node (ref "J2") (pin "13") (pinfunction "13_13") (pintype "passive"))
      (node (ref "U1") (pin "32") (pinfunction "GPIO36/_SPIIO7/_FSPICLK/_SUBSPICLK_32") (pintype "passive"))
    )
    (net (code "51") (name "/GPIO37") (class "Default")
      (node (ref "J2") (pin "12") (pinfunction "12_12") (pintype "passive"))
      (node (ref "U1") (pin "33") (pinfunction "GPIO37/_SPIDQS/_FSPIQ/_SUBSPIQ_33") (pintype "passive"))
    )
    (net (code "52") (name "/GPIO38") (class "Default")
      (node (ref "J2") (pin "11") (pinfunction "11_11") (pintype "passive"))
      (node (ref "U1") (pin "34") (pinfunction "GPIO38/_FSPIWP/_SUBSPIWP_34") (pintype "passive"))
    )
    (net (code "53") (name "/GPIO39") (class "Default")
      (node (ref "J2") (pin "10") (pinfunction "10_10") (pintype "passive"))
      (node (ref "U1") (pin "35") (pinfunction "GPIO39/_MTCK/_CLK_OUT3/_SUBSPICS1_35") (pintype "passive"))
    )
    (net (code "54") (name "/GPIO40") (class "Default")
      (node (ref "J2") (pin "9") (pinfunction "9_9") (pintype "passive"))
      (node (ref "U1") (pin "36") (pinfunction "GPIO40/_MTDO/_CLK_OUT2_36") (pintype "passive"))
    )
    (net (code "55") (name "/GPIO41") (class "Default")
      (node (ref "J2") (pin "8") (pinfunction "8_8") (pintype "passive"))
      (node (ref "U1") (pin "37") (pinfunction "GPIO41/_MTDI/_CLK_OUT1_37") (pintype "passive"))
    )
    (net (code "56") (name "/GPIO42") (class "Default")
      (node (ref "J2") (pin "7") (pinfunction "7_7") (pintype "passive"))
      (node (ref "U1") (pin "38") (pinfunction "GPIO42,_MTMS_38") (pintype "passive"))
    )
    (net (code "57") (name "/GPIO45") (class "Default")
      (node (ref "J2") (pin "4") (pinfunction "4_4") (pintype "passive"))
      (node (ref "U1") (pin "41") (pinfunction "GPIO45_41") (pintype "passive"))
    )
    (net (code "58") (name "/GPIO46") (class "Default")
      (node (ref "J2") (pin "3") (pinfunction "3_3") (pintype "passive"))
      (node (ref "U1") (pin "44") (pinfunction "GPIO46_44") (pintype "passive"))
    )
    (net (code "59") (name "/GPIO47") (class "Default")
      (node (ref "J2") (pin "22") (pinfunction "22_22") (pintype "passive"))
      (node (ref "U1") (pin "27") (pinfunction "GPIO47/_SPICLK_P_DIFF/_SUBSPICLK_P_DIFF_27") (pintype "passive"))
    )
    (net (code "60") (name "/GPIO48") (class "Default")
      (node (ref "J2") (pin "21") (pinfunction "21_21") (pintype "passive"))
      (node (ref "U1") (pin "30") (pinfunction "GPIO48/_SPICLK_N_DIFF/_SUBSPICLK_N_DIFF_30") (pintype "passive"))
    )
    (net (code "61") (name "/U0RXD") (class "Default")
      (node (ref "J2") (pin "5") (pinfunction "5_5") (pintype "passive"))
      (node (ref "R21") (pin "1") (pinfunction "1_1") (pintype "passive"))
      (node (ref "U1") (pin "40") (pinfunction "GPIO44,_U0RXD,_CLK_OUT2_40") (pintype "passive"))
    )
    (net (code "62") (name "/U0TXD") (class "Default")
      (node (ref "J2") (pin "6") (pinfunction "6_6") (pintype "passive"))
      (node (ref "R22") (pin "1") (pinfunction "1_1") (pintype "passive"))
      (node (ref "U1") (pin "39") (pinfunction "GPIO43,_U0TXD,_CLK_OUT1_39") (pintype "passive"))
    )
    (net (code "63") (name "/VBUS SENSE") (class "Default")
      (node (ref "R10") (pin "1") (pinfunction "1_1") (pintype "passive"))
      (node (ref "R11") (pin "2") (pinfunction "2_2") (pintype "passive"))
      (node (ref "U2") (pin "16") (pinfunction "CBUS3_16") (pintype "passive"))
    )
    (net (code "64") (name "GND") (class "Default")
      (node (ref "C1") (pin "1") (pinfunction "1_1") (pintype "passive"))
      (node (ref "C10") (pin "1") (pinfunction "1_1") (pintype "passive"))
      (node (ref "C11") (pin "1") (pinfunction "1_1") (pintype "passive"))
      (node (ref "C12") (pin "1") (pinfunction "1_1") (pintype "passive"))
      (node (ref "C13") (pin "1") (pinfunction "1_1") (pintype "passive"))
      (node (ref "C14") (pin "1") (pinfunction "1_1") (pintype "passive"))
      (node (ref "C15") (pin "1") (pinfunction "1_1") (pintype "passive"))
      (node (ref "C16") (pin "1") (pinfunction "1_1") (pintype "passive"))
      (node (ref "C2") (pin "1") (pinfunction "1_1") (pintype "passive"))
      (node (ref "C3") (pin "1") (pinfunction "1_1") (pintype "passive"))
      (node (ref "C4") (pin "1") (pinfunction "1_1") (pintype "passive"))
      (node (ref "C5") (pin "1") (pinfunction "1_1") (pintype "passive"))
      (node (ref "C6") (pin "1") (pinfunction "1_1") (pintype "passive"))
      (node (ref "C7") (pin "1") (pinfunction "1_1") (pintype "passive"))
      (node (ref "C8") (pin "1") (pinfunction "1_1") (pintype "passive"))
      (node (ref "C9") (pin "1") (pinfunction "1_1") (pintype "passive"))
      (node (ref "D1") (pin "1") (pinfunction "1_1") (pintype "passive"))
      (node (ref "D2") (pin "1") (pinfunction "1_1") (pintype "passive"))
      (node (ref "D3") (pin "1") (pinfunction "1_1") (pintype "passive"))
      (node (ref "D4") (pin "1") (pinfunction "1_1") (pintype "passive"))
      (node (ref "D5") (pin "1") (pinfunction "1_1") (pintype "passive"))
      (node (ref "D6") (pin "1") (pinfunction "1_1") (pintype "passive"))
      (node (ref "D8") (pin "2") (pinfunction "2_2") (pintype "passive"))
      (node (ref "J1") (pin "22") (pinfunction "22_22") (pintype "passive"))
      (node (ref "J2") (pin "1") (pinfunction "1_1") (pintype "passive"))
      (node (ref "J3") (pin "A1B12") (pinfunction "GND_A1B12_A1B12") (pintype "passive"))
      (node (ref "J3") (pin "B1A12") (pinfunction "GND_B1A12_B1A12") (pintype "passive"))
      (node (ref "J3") (pin "S1") (pinfunction "SHIELD_1_S1") (pintype "passive"))
      (node (ref "J3") (pin "S2") (pinfunction "SHIELD_2_S2") (pintype "passive"))
      (node (ref "J3") (pin "S3") (pinfunction "SHIELD_3_S3") (pintype "passive"))
      (node (ref "J3") (pin "S4") (pinfunction "SHIELD_4_S4") (pintype "passive"))
      (node (ref "J4") (pin "A1B12") (pinfunction "GND_A1B12_A1B12") (pintype "passive"))
      (node (ref "J4") (pin "B1A12") (pinfunction "GND_B1A12_B1A12") (pintype "passive"))
      (node (ref "J4") (pin "S1") (pinfunction "SHIELD_1_S1") (pintype "passive"))
      (node (ref "J4") (pin "S2") (pinfunction "SHIELD_2_S2") (pintype "passive"))
      (node (ref "J4") (pin "S3") (pinfunction "SHIELD_3_S3") (pintype "passive"))
      (node (ref "J4") (pin "S4") (pinfunction "SHIELD_4_S4") (pintype "passive"))
      (node (ref "R11") (pin "1") (pinfunction "1_1") (pintype "passive"))
      (node (ref "R14") (pin "1") (pinfunction "1_1") (pintype "passive"))
      (node (ref "R15") (pin "1") (pinfunction "1_1") (pintype "passive"))
      (node (ref "R5") (pin "1") (pinfunction "1_1") (pintype "passive"))
      (node (ref "R6") (pin "1") (pinfunction "1_1") (pintype "passive"))
      (node (ref "R9") (pin "2") (pinfunction "2_2") (pintype "passive"))
      (node (ref "SW1") (pin "1") (pinfunction "1_1") (pintype "passive"))
      (node (ref "SW1") (pin "2") (pinfunction "2_2") (pintype "passive"))
      (node (ref "SW2") (pin "1") (pinfunction "1_1") (pintype "passive"))
      (node (ref "SW2") (pin "2") (pinfunction "2_2") (pintype "passive"))
      (node (ref "U1") (pin "1") (pinfunction "GND_1") (pintype "passive"))
      (node (ref "U1") (pin "2") (pinfunction "GND_2") (pintype "passive"))
      (node (ref "U1") (pin "42") (pinfunction "GND_42") (pintype "passive"))
      (node (ref "U1") (pin "43") (pinfunction "GND_43") (pintype "passive"))
      (node (ref "U1") (pin "46") (pinfunction "GND_46") (pintype "passive"))
      (node (ref "U1") (pin "47") (pinfunction "GND_47") (pintype "passive"))
      (node (ref "U1") (pin "48") (pinfunction "GND_48") (pintype "passive"))
      (node (ref "U1") (pin "49") (pinfunction "GND_49") (pintype "passive"))
      (node (ref "U1") (pin "50") (pinfunction "GND_50") (pintype "passive"))
      (node (ref "U1") (pin "51") (pinfunction "GND_51") (pintype "passive"))
      (node (ref "U1") (pin "52") (pinfunction "GND_52") (pintype "passive"))
      (node (ref "U1") (pin "53") (pinfunction "GND_53") (pintype "passive"))
      (node (ref "U1") (pin "54") (pinfunction "GND_54") (pintype "passive"))
      (node (ref "U1") (pin "55") (pinfunction "GND_55") (pintype "passive"))
      (node (ref "U1") (pin "56") (pinfunction "GND_56") (pintype "passive"))
      (node (ref "U1") (pin "57") (pinfunction "GND_57") (pintype "passive"))
      (node (ref "U1") (pin "58") (pinfunction "GND_58") (pintype "passive"))
      (node (ref "U1") (pin "59") (pinfunction "GND_59") (pintype "passive"))
      (node (ref "U1") (pin "60") (pinfunction "GND_60") (pintype "passive"))
      (node (ref "U1") (pin "61") (pinfunction "GND_61") (pintype "passive"))
      (node (ref "U1") (pin "62") (pinfunction "GND_62") (pintype "passive"))
      (node (ref "U1") (pin "63") (pinfunction "GND_63") (pintype "passive"))
      (node (ref "U1") (pin "64") (pinfunction "GND_64") (pintype "passive"))
      (node (ref "U1") (pin "65") (pinfunction "GND_65") (pintype "passive"))
      (node (ref "U1") (pin "66") (pinfunction "GND_66") (pintype "passive"))
      (node (ref "U1") (pin "67") (pinfunction "GND_67") (pintype "passive"))
      (node (ref "U1") (pin "68") (pinfunction "GND_68") (pintype "passive"))
      (node (ref "U1") (pin "69") (pinfunction "GND_69") (pintype "passive"))
      (node (ref "U1") (pin "70") (pinfunction "GND_70") (pintype "passive"))
      (node (ref "U1") (pin "71") (pinfunction "GND_71") (pintype "passive"))
      (node (ref "U1") (pin "72") (pinfunction "GND_72") (pintype "passive"))
      (node (ref "U1") (pin "73") (pinfunction "GND_73") (pintype "passive"))
      (node (ref "U2") (pin "13") (pinfunction "GND_13") (pintype "passive"))
      (node (ref "U2") (pin "21") (pinfunction "GND_21") (pintype "passive"))
      (node (ref "U2") (pin "3") (pinfunction "GND_3") (pintype "passive"))
      (node (ref "U3") (pin "2") (pinfunction "GND_2") (pintype "power_in"))
      (node (ref "U3") (pin "4") (pinfunction "GND_4") (pintype "power_in"))
    )
    (net (code "65") (name "Net-(D7-Pad1)") (class "Default")
      (node (ref "D7") (pin "1") (pinfunction "1_1") (pintype "passive"))
      (node (ref "R19") (pin "1") (pinfunction "1_1") (pintype "passive"))
    )
    (net (code "66") (name "Net-(D8-Pad1)") (class "Default")
      (node (ref "D8") (pin "1") (pinfunction "1_1") (pintype "passive"))
      (node (ref "R20") (pin "1") (pinfunction "1_1") (pintype "passive"))
    )
    (net (code "67") (name "Net-(J3-CC1)") (class "Default")
      (node (ref "J3") (pin "A5") (pinfunction "CC1_A5") (pintype "passive"))
      (node (ref "R6") (pin "2") (pinfunction "2_2") (pintype "passive"))
    )
    (net (code "68") (name "Net-(J3-CC2)") (class "Default")
      (node (ref "J3") (pin "B5") (pinfunction "CC2_B5") (pintype "passive"))
      (node (ref "R5") (pin "2") (pinfunction "2_2") (pintype "passive"))
    )
    (net (code "69") (name "Net-(J4-CC1)") (class "Default")
      (node (ref "J4") (pin "A5") (pinfunction "CC1_A5") (pintype "passive"))
      (node (ref "R15") (pin "2") (pinfunction "2_2") (pintype "passive"))
    )
    (net (code "70") (name "Net-(J4-CC2)") (class "Default")
      (node (ref "J4") (pin "B5") (pinfunction "CC2_B5") (pintype "passive"))
      (node (ref "R14") (pin "2") (pinfunction "2_2") (pintype "passive"))
    )
    (net (code "71") (name "Net-(Q1-B)") (class "Default")
      (node (ref "Q1") (pin "1") (pinfunction "B_1") (pintype "passive"))
      (node (ref "R13") (pin "2") (pinfunction "2_2") (pintype "passive"))
    )
    (net (code "72") (name "Net-(Q1-C)") (class "Default")
      (node (ref "Q1") (pin "3") (pinfunction "C_3") (pintype "passive"))
      (node (ref "R12") (pin "1") (pinfunction "1_1") (pintype "passive"))
    )
    (net (code "73") (name "Net-(Q2-B)") (class "Default")
      (node (ref "Q2") (pin "1") (pinfunction "B_1") (pintype "passive"))
      (node (ref "R16") (pin "2") (pinfunction "2_2") (pintype "passive"))
    )
    (net (code "74") (name "Net-(Q2-C)") (class "Default")
      (node (ref "Q2") (pin "3") (pinfunction "C_3") (pintype "passive"))
      (node (ref "R17") (pin "1") (pinfunction "1_1") (pintype "passive"))
    )
    (net (code "75") (name "Net-(U2-CBUS0)") (class "Default")
      (node (ref "R9") (pin "1") (pinfunction "1_1") (pintype "passive"))
      (node (ref "U2") (pin "15") (pinfunction "CBUS0_15") (pintype "passive"))
    )
    (net (code "76") (name "unconnected-(J3-SBU1-PadA8)") (class "Default")
      (node (ref "J3") (pin "A8") (pinfunction "SBU1_A8") (pintype "passive+no_connect"))
    )
    (net (code "77") (name "unconnected-(J3-SBU2-PadB8)") (class "Default")
      (node (ref "J3") (pin "B8") (pinfunction "SBU2_B8") (pintype "passive+no_connect"))
    )
    (net (code "78") (name "unconnected-(J4-SBU1-PadA8)") (class "Default")
      (node (ref "J4") (pin "A8") (pinfunction "SBU1_A8") (pintype "passive+no_connect"))
    )
    (net (code "79") (name "unconnected-(J4-SBU2-PadB8)") (class "Default")
      (node (ref "J4") (pin "B8") (pinfunction "SBU2_B8") (pintype "passive+no_connect"))
    )
    (net (code "80") (name "unconnected-(U2-CBUS1-Pad14)") (class "Default")
      (node (ref "U2") (pin "14") (pinfunction "CBUS1_14") (pintype "passive"))
    )
    (net (code "81") (name "unconnected-(U2-CBUS2-Pad7)") (class "Default")
      (node (ref "U2") (pin "7") (pinfunction "CBUS2_7") (pintype "passive"))
    )
    (net (code "82") (name "unconnected-(U2-~{CTS}-Pad6)") (class "Default")
      (node (ref "U2") (pin "6") (pinfunction "~{CTS}_6") (pintype "passive+no_connect"))
    )
    (net (code "83") (name "unconnected-(U2-~{DCD}-Pad5)") (class "Default")
      (node (ref "U2") (pin "5") (pinfunction "~{DCD}_5") (pintype "passive+no_connect"))
    )
    (net (code "84") (name "unconnected-(U2-~{DSR}-Pad4)") (class "Default")
      (node (ref "U2") (pin "4") (pinfunction "~{DSR}_4") (pintype "passive+no_connect"))
    )
    (net (code "85") (name "unconnected-(U2-~{RI}-Pad2)") (class "Default")
      (node (ref "U2") (pin "2") (pinfunction "~{RI}_2") (pintype "passive+no_connect"))
    )
  )
)
